# Thesis_Schematic.net
KiCad netlist of a schematic drawn in Altium Designer
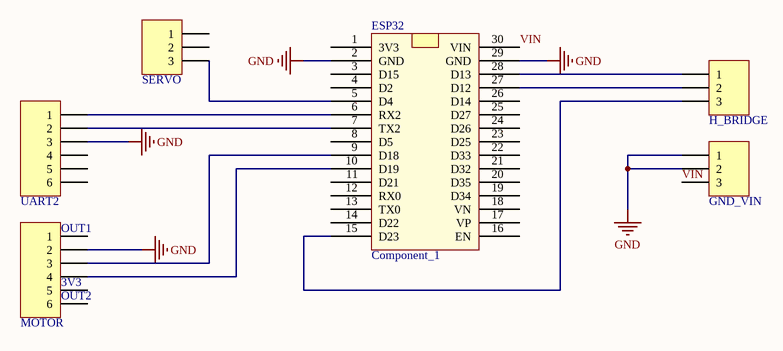
[diagram p0: Thesis_Schematic.SchDoc]

(export (version "E")
  (design (tool "Eeschema 10.0.6"))
  (components
    (comp (ref "ESP32")
      (value "Component_1")
      (footprint "ESP32")
      (libsource (lib "ESP32_SCH") (part "Component_1"))
    )
    (comp (ref "GND_VIN")
      (value "Header 3")
      (footprint "JP3")
      (description "Header, 3-Pin")
      (fields (field (name "PUBLISHER") "Altium Limited"))
      (libsource (lib "PIF_Library") (part "Header 3"))
    )
    (comp (ref "H_BRIDGE")
      (value "Header 3")
      (footprint "JP3")
      (description "Header, 3-Pin")
      (fields (field (name "PUBLISHER") "Altium Limited"))
      (libsource (lib "PIF_Library") (part "Header 3"))
    )
    (comp (ref "MOTOR")
      (value "Header 6")
      (footprint "JP6")
      (description "Header, 6-Pin")
      (fields (field (name "PUBLISHER") "Altium Limited"))
      (libsource (lib "PIF_Library") (part "Header 6"))
    )
    (comp (ref "SERVO")
      (value "Header 3")
      (footprint "JP3")
      (description "Header, 3-Pin")
      (fields (field (name "PUBLISHER") "Altium Limited"))
      (libsource (lib "") (part "Header 3_1"))
    )
    (comp (ref "UART2")
      (value "Header 6")
      (footprint "JP6")
      (description "Header, 6-Pin")
      (fields (field (name "PUBLISHER") "Altium Limited"))
      (libsource (lib "PIF_Library") (part "Header 6"))
    )
  )
  (nets
    (net (code "1") (name "/VIN") (class "Default")
      (node (ref "ESP32") (pin "30") (pinfunction "VIN_30") (pintype "passive"))
      (node (ref "GND_VIN") (pin "3") (pinfunction "3_3") (pintype "passive"))
    )
    (net (code "2") (name "GND") (class "Default")
      (node (ref "ESP32") (pin "2") (pinfunction "GND_2") (pintype "passive"))
      (node (ref "ESP32") (pin "29") (pinfunction "GND_29") (pintype "passive"))
      (node (ref "GND_VIN") (pin "1") (pinfunction "1_1") (pintype "passive"))
      (node (ref "GND_VIN") (pin "2") (pinfunction "2_2") (pintype "passive"))
      (node (ref "MOTOR") (pin "2") (pinfunction "2_2") (pintype "passive"))
      (node (ref "UART2") (pin "3") (pinfunction "3_3") (pintype "passive"))
    )
    (net (code "3") (name "Net-(ESP32-D4)") (class "Default")
      (node (ref "ESP32") (pin "5") (pinfunction "D4_5") (pintype "passive"))
      (node (ref "SERVO") (pin "3") (pinfunction "3_3") (pintype "passive"))
    )
    (net (code "4") (name "Net-(ESP32-D12)") (class "Default")
      (node (ref "ESP32") (pin "27") (pinfunction "D12_27") (pintype "passive"))
      (node (ref "H_BRIDGE") (pin "2") (pinfunction "2_2") (pintype "passive"))
    )
    (net (code "5") (name "Net-(ESP32-D13)") (class "Default")
      (node (ref "ESP32") (pin "28") (pinfunction "D13_28") (pintype "passive"))
      (node (ref "H_BRIDGE") (pin "1") (pinfunction "1_1") (pintype "passive"))
    )
    (net (code "6") (name "Net-(ESP32-D18)") (class "Default")
      (node (ref "ESP32") (pin "9") (pinfunction "D18_9") (pintype "passive"))
      (node (ref "MOTOR") (pin "3") (pinfunction "3_3") (pintype "passive"))
    )
    (net (code "7") (name "Net-(ESP32-D19)") (class "Default")
      (node (ref "ESP32") (pin "10") (pinfunction "D19_10") (pintype "passive"))
      (node (ref "MOTOR") (pin "4") (pinfunction "4_4") (pintype "passive"))
    )
    (net (code "8") (name "Net-(ESP32-D23)") (class "Default")
      (node (ref "ESP32") (pin "15") (pinfunction "D23_15") (pintype "passive"))
      (node (ref "H_BRIDGE") (pin "3") (pinfunction "3_3") (pintype "passive"))
    )
    (net (code "9") (name "Net-(ESP32-RX2)") (class "Default")
      (node (ref "ESP32") (pin "6") (pinfunction "RX2_6") (pintype "passive"))
      (node (ref "UART2") (pin "1") (pinfunction "1_1") (pintype "passive"))
    )
    (net (code "10") (name "Net-(ESP32-TX2)") (class "Default")
      (node (ref "ESP32") (pin "7") (pinfunction "TX2_7") (pintype "passive"))
      (node (ref "UART2") (pin "2") (pinfunction "2_2") (pintype "passive"))
    )
    (net (code "11") (name "unconnected-(ESP32-3V3-Pad1)") (class "Default")
      (node (ref "ESP32") (pin "1") (pinfunction "3V3_1") (pintype "passive"))
    )
    (net (code "12") (name "unconnected-(ESP32-D2-Pad4)") (class "Default")
      (node (ref "ESP32") (pin "4") (pinfunction "D2_4") (pintype "passive"))
    )
    (net (code "13") (name "unconnected-(ESP32-D5-Pad8)") (class "Default")
      (node (ref "ESP32") (pin "8") (pinfunction "D5_8") (pintype "passive"))
    )
    (net (code "14") (name "unconnected-(ESP32-D14-Pad26)") (class "Default")
      (node (ref "ESP32") (pin "26") (pinfunction "D14_26") (pintype "passive"))
    )
    (net (code "15") (name "unconnected-(ESP32-D15-Pad3)") (class "Default")
      (node (ref "ESP32") (pin "3") (pinfunction "D15_3") (pintype "passive"))
    )
    (net (code "16") (name "unconnected-(ESP32-D21-Pad11)") (class "Default")
      (node (ref "ESP32") (pin "11") (pinfunction "D21_11") (pintype "passive"))
    )
    (net (code "17") (name "unconnected-(ESP32-D22-Pad14)") (class "Default")
      (node (ref "ESP32") (pin "14") (pinfunction "D22_14") (pintype "passive"))
    )
    (net (code "18") (name "unconnected-(ESP32-D25-Pad23)") (class "Default")
      (node (ref "ESP32") (pin "23") (pinfunction "D25_23") (pintype "passive"))
    )
    (net (code "19") (name "unconnected-(ESP32-D26-Pad24)") (class "Default")
      (node (ref "ESP32") (pin "24") (pinfunction "D26_24") (pintype "passive"))
    )
    (net (code "20") (name "unconnected-(ESP32-D27-Pad25)") (class "Default")
      (node (ref "ESP32") (pin "25") (pinfunction "D27_25") (pintype "passive"))
    )
    (net (code "21") (name "unconnected-(ESP32-D32-Pad21)") (class "Default")
      (node (ref "ESP32") (pin "21") (pinfunction "D32_21") (pintype "passive"))
    )
    (net (code "22") (name "unconnected-(ESP32-D33-Pad22)") (class "Default")
      (node (ref "ESP32") (pin "22") (pinfunction "D33_22") (pintype "passive"))
    )
    (net (code "23") (name "unconnected-(ESP32-D34-Pad19)") (class "Default")
      (node (ref "ESP32") (pin "19") (pinfunction "D34_19") (pintype "passive"))
    )
    (net (code "24") (name "unconnected-(ESP32-D35-Pad20)") (class "Default")
      (node (ref "ESP32") (pin "20") (pinfunction "D35_20") (pintype "passive"))
    )
    (net (code "25") (name "unconnected-(ESP32-EN-Pad16)") (class "Default")
      (node (ref "ESP32") (pin "16") (pinfunction "EN_16") (pintype "passive"))
    )
    (net (code "26") (name "unconnected-(ESP32-RX0-Pad12)") (class "Default")
      (node (ref "ESP32") (pin "12") (pinfunction "RX0_12") (pintype "passive"))
    )
    (net (code "27") (name "unconnected-(ESP32-TX0-Pad13)") (class "Default")
      (node (ref "ESP32") (pin "13") (pinfunction "TX0_13") (pintype "passive"))
    )
    (net (code "28") (name "unconnected-(ESP32-VN-Pad18)") (class "Default")
      (node (ref "ESP32") (pin "18") (pinfunction "VN_18") (pintype "passive"))
    )
    (net (code "29") (name "unconnected-(ESP32-VP-Pad17)") (class "Default")
      (node (ref "ESP32") (pin "17") (pinfunction "VP_17") (pintype "passive"))
    )
    (net (code "30") (name "unconnected-(MOTOR-Pad1)") (class "Default")
      (node (ref "MOTOR") (pin "1") (pinfunction "1_1") (pintype "passive"))
    )
    (net (code "31") (name "unconnected-(MOTOR-Pad5)") (class "Default")
      (node (ref "MOTOR") (pin "5") (pinfunction "5_5") (pintype "passive"))
    )
    (net (code "32") (name "unconnected-(MOTOR-Pad6)") (class "Default")
      (node (ref "MOTOR") (pin "6") (pinfunction "6_6") (pintype "passive"))
    )
    (net (code "33") (name "unconnected-(SERVO-Pad1)") (class "Default")
      (node (ref "SERVO") (pin "1") (pinfunction "1_1") (pintype "passive"))
    )
    (net (code "34") (name "unconnected-(SERVO-Pad2)") (class "Default")
      (node (ref "SERVO") (pin "2") (pinfunction "2_2") (pintype "passive"))
    )
    (net (code "35") (name "unconnected-(UART2-Pad4)") (class "Default")
      (node (ref "UART2") (pin "4") (pinfunction "4_4") (pintype "passive"))
    )
    (net (code "36") (name "unconnected-(UART2-Pad5)") (class "Default")
      (node (ref "UART2") (pin "5") (pinfunction "5_5") (pintype "passive"))
    )
    (net (code "37") (name "unconnected-(UART2-Pad6)") (class "Default")
      (node (ref "UART2") (pin "6") (pinfunction "6_6") (pintype "passive"))
    )
  )
)
